# main.net
KiCad netlist of a schematic drawn in Altium Designer
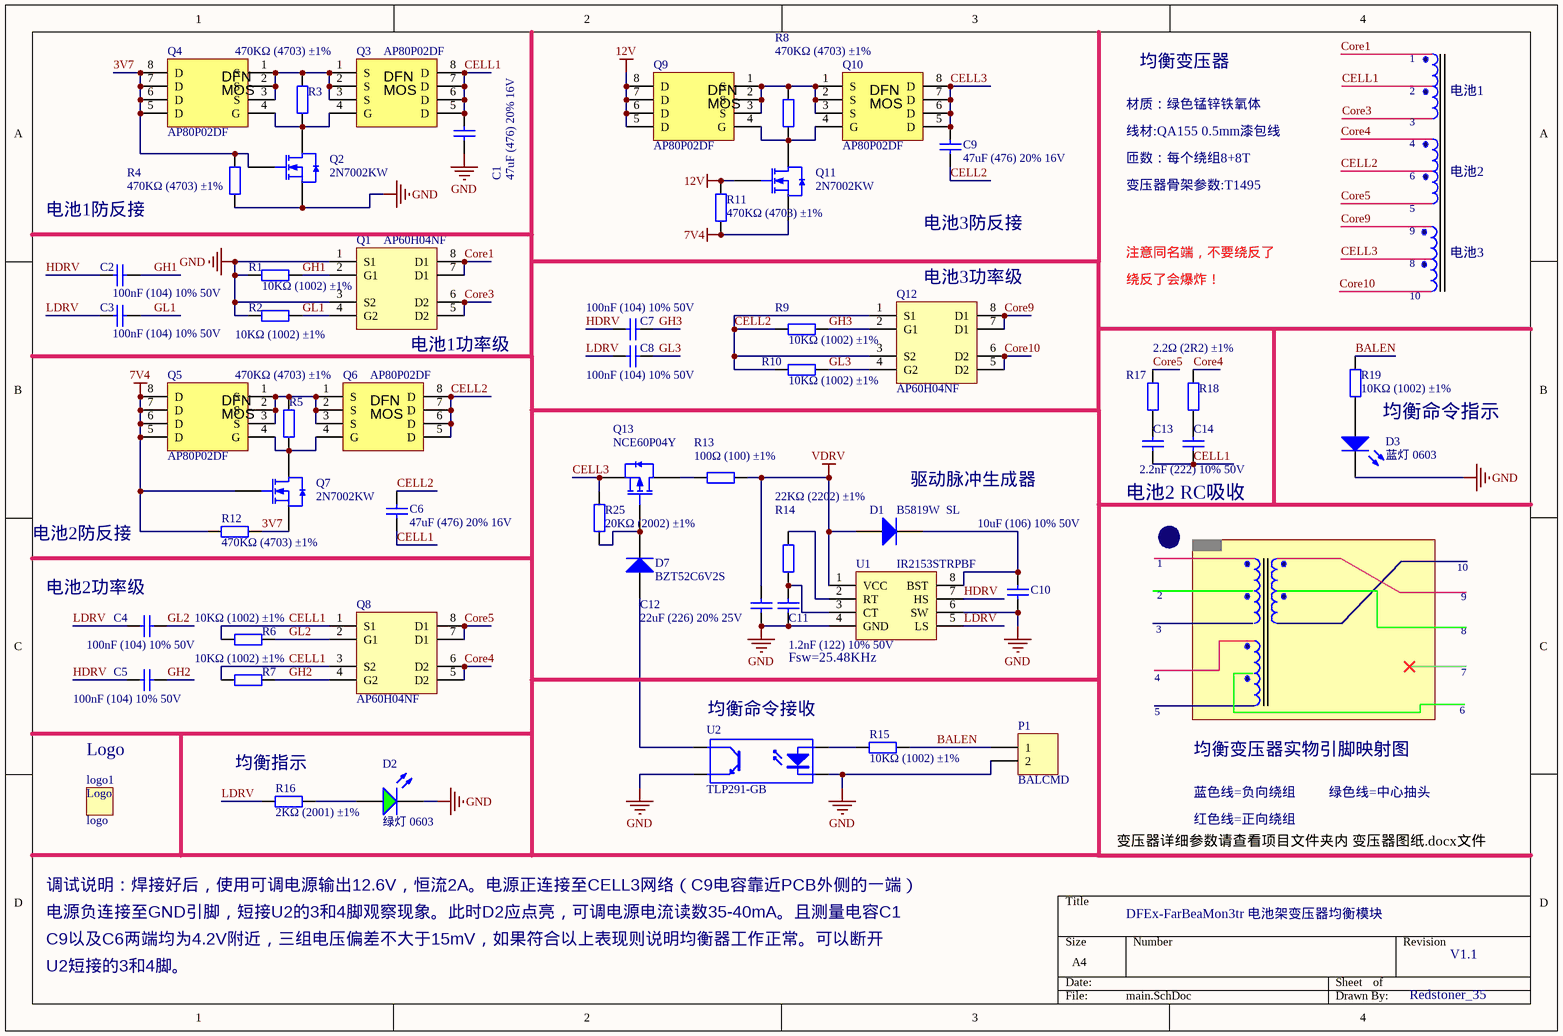
[diagram p0: main.SchDoc]

(export (version "E")
  (design (tool "Eeschema 10.0.6"))
  (components
    (comp (ref "C1")
      (value "47uF (476) 20% 16V")
      (footprint "1206_C")
      (description "贴片电容")
      (libsource (lib "Miscellaneous Devices LC") (part "1206 220pF (221) 10% 50V"))
    )
    (comp (ref "C2")
      (value "100nF (104) 10% 50V")
      (footprint "1206_C")
      (description "贴片电容")
      (libsource (lib "Miscellaneous Devices LC") (part "1206 100nF (104) 10% 50V"))
    )
    (comp (ref "C3")
      (value "100nF (104) 10% 50V")
      (footprint "1206_C")
      (description "贴片电容")
      (libsource (lib "Miscellaneous Devices LC") (part "1206 100nF (104) 10% 50V"))
    )
    (comp (ref "C4")
      (value "100nF (104) 10% 50V")
      (footprint "1206_C")
      (description "贴片电容")
      (libsource (lib "Miscellaneous Devices LC") (part "1206 100nF (104) 10% 50V"))
    )
    (comp (ref "C5")
      (value "100nF (104) 10% 50V")
      (footprint "1206_C")
      (description "贴片电容")
      (libsource (lib "Miscellaneous Devices LC") (part "1206 100nF (104) 10% 50V"))
    )
    (comp (ref "C6")
      (value "47uF (476) 20% 16V")
      (footprint "1206_C")
      (description "贴片电容")
      (libsource (lib "Miscellaneous Devices LC") (part "1206 220pF (221) 10% 50V"))
    )
    (comp (ref "C7")
      (value "100nF (104) 10% 50V")
      (footprint "1206_C")
      (description "贴片电容")
      (libsource (lib "Miscellaneous Devices LC") (part "1206 100nF (104) 10% 50V"))
    )
    (comp (ref "C8")
      (value "100nF (104) 10% 50V")
      (footprint "1206_C")
      (description "贴片电容")
      (libsource (lib "Miscellaneous Devices LC") (part "1206 100nF (104) 10% 50V"))
    )
    (comp (ref "C9")
      (value "47uF (476) 20% 16V")
      (footprint "1206_C")
      (description "贴片电容")
      (libsource (lib "Miscellaneous Devices LC") (part "1206 220pF (221) 10% 50V"))
    )
    (comp (ref "C10")
      (value "10uF (106) 10% 50V")
      (footprint "1206_C")
      (description "贴片电容")
      (libsource (lib "Miscellaneous Devices LC") (part "1206 10uF (106) 10% 50V"))
    )
    (comp (ref "C11")
      (value "1.2nF (122) 10% 50V")
      (footprint "0402_C")
      (description "贴片电容")
      (libsource (lib "Miscellaneous Devices LC") (part "0402 1nF (102) 10% 50V"))
    )
    (comp (ref "C12")
      (value "22uF (226) 20% 25V")
      (footprint "0805_C")
      (description "贴片电容")
      (libsource (lib "Miscellaneous Devices LC") (part "0805 22uF (226) 20% 25V"))
    )
    (comp (ref "C13")
      (value "2.2nF (222) 10% 50V")
      (footprint "0402_C")
      (description "贴片电容")
      (libsource (lib "Miscellaneous Devices LC") (part "0402 2.2nF (222) 10% 50V"))
    )
    (comp (ref "C14")
      (value "2.2nF (222) 10% 50V")
      (footprint "0402_C")
      (description "贴片电容")
      (libsource (lib "Miscellaneous Devices LC") (part "0402 2.2nF (222) 10% 50V"))
    )
    (comp (ref "D1")
      (value "B5819W  SL")
      (footprint "SOD-123")
      (description "肖特基二极管")
      (libsource (lib "Miscellaneous Devices LC") (part "SOD-123 B5819W  SL"))
    )
    (comp (ref "D2")
      (value "绿灯 0603")
      (footprint "0603_LED_S1")
      (description "发光二极管")
      (libsource (lib "Miscellaneous Devices LC") (part "0603 绿灯"))
    )
    (comp (ref "D3")
      (value "蓝灯 0603")
      (footprint "0603_LED_S1")
      (description "发光二极管")
      (libsource (lib "Miscellaneous Devices LC") (part "0603 蓝灯"))
    )
    (comp (ref "D7")
      (value "BZT52C6V2S")
      (footprint "SOD-323")
      (description "SOD-323稳压二极管 6.2V稳压电压")
      (libsource (lib "Miscellaneous Devices LC") (part "SOD-323 1N4148WS T4"))
    )
    (comp (ref "logo1")
      (value "logo")
      (footprint "HIGH-VOLTAGE-2")
      (libsource (lib "山猫的集成库20190318") (part "logo"))
    )
    (comp (ref "P1")
      (value "BALCMD")
      (footprint "PH2.0-WS-2P")
      (description "2-Pin")
      (fields (field (name "PUBLISHER") "Altium Limited"))
      (libsource (lib "山猫的集成库20190318") (part "CON 2"))
    )
    (comp (ref "Q1")
      (value "AP60H04NF")
      (footprint "Dual SSO8")
      (description "APM双N沟道MOS管，DFN56封装，40V/60A 4.8mΩ/4.5V Vgs")
      (libsource (lib "custom") (part "AP60H04NF"))
    )
    (comp (ref "Q2")
      (value "2N7002KW")
      (footprint "SC70-3")
      (description "单N沟道MOSFET(场效应管)")
      (libsource (lib "Miscellaneous Devices LC") (part "2N7002 7002"))
    )
    (comp (ref "Q3")
      (value "AP80P02DF")
      (footprint "DFN-8_L3.0-W3.0-P0.65-BL")
      (description "PDFN3x3 20V 50A 5.8mΩ N-Ch MOSFET")
      (libsource (lib "custom") (part "SON/DFN5x6 MOS"))
    )
    (comp (ref "Q4")
      (value "AP80P02DF")
      (footprint "DFN-8_L3.0-W3.0-P0.65-BL")
      (description "PDFN3x3 20V 50A 5.8mΩ N-Ch MOSFET")
      (libsource (lib "") (part "SON/DFN5x6 MOS_1"))
    )
    (comp (ref "Q5")
      (value "AP80P02DF")
      (footprint "DFN-8_L3.0-W3.0-P0.65-BL")
      (description "PDFN3x3 20V 50A 5.8mΩ N-Ch MOSFET")
      (libsource (lib "") (part "SON/DFN5x6 MOS_1"))
    )
    (comp (ref "Q6")
      (value "AP80P02DF")
      (footprint "DFN-8_L3.0-W3.0-P0.65-BL")
      (description "PDFN3x3 20V 50A 5.8mΩ N-Ch MOSFET")
      (libsource (lib "custom") (part "SON/DFN5x6 MOS"))
    )
    (comp (ref "Q7")
      (value "2N7002KW")
      (footprint "SC70-3")
      (description "单N沟道MOSFET(场效应管)")
      (libsource (lib "Miscellaneous Devices LC") (part "2N7002 7002"))
    )
    (comp (ref "Q8")
      (value "AP60H04NF")
      (footprint "Dual SSO8")
      (description "APM双N沟道MOS管，DFN56封装，40V/60A 4.8mΩ/4.5V Vgs")
      (libsource (lib "custom") (part "AP60H04NF"))
    )
    (comp (ref "Q9")
      (value "AP80P02DF")
      (footprint "DFN-8_L3.0-W3.0-P0.65-BL")
      (description "PDFN3x3 20V 50A 5.8mΩ N-Ch MOSFET")
      (libsource (lib "") (part "SON/DFN5x6 MOS_1"))
    )
    (comp (ref "Q10")
      (value "AP80P02DF")
      (footprint "DFN-8_L3.0-W3.0-P0.65-BL")
      (description "PDFN3x3 20V 50A 5.8mΩ N-Ch MOSFET")
      (libsource (lib "custom") (part "SON/DFN5x6 MOS"))
    )
    (comp (ref "Q11")
      (value "2N7002KW")
      (footprint "SC70-3")
      (description "单N沟道MOSFET(场效应管)")
      (libsource (lib "Miscellaneous Devices LC") (part "2N7002 7002"))
    )
    (comp (ref "Q12")
      (value "AP60H04NF")
      (footprint "Dual SSO8")
      (description "APM双N沟道MOS管，DFN56封装，40V/60A 4.8mΩ/4.5V Vgs")
      (libsource (lib "custom") (part "AP60H04NF"))
    )
    (comp (ref "Q13")
      (value "NCE60P04Y")
      (footprint "SOT-23(SOT-23-3)")
      (description "MOS(场效应管)")
      (libsource (lib "Miscellaneous Devices LC") (part "SI2301CDS-T1-GE3"))
    )
    (comp (ref "R1")
      (value "10KΩ (1002) ±1%")
      (footprint "0402_R")
      (description "贴片电阻")
      (libsource (lib "Miscellaneous Devices LC") (part "0402 10KΩ (1002) 1%"))
    )
    (comp (ref "R2")
      (value "10KΩ (1002) ±1%")
      (footprint "0402_R")
      (description "贴片电阻")
      (libsource (lib "Miscellaneous Devices LC") (part "0402 10KΩ (1002) 1%"))
    )
    (comp (ref "R3")
      (value "470KΩ (4703) ±1%")
      (footprint "0402_R")
      (description "贴片电阻")
      (libsource (lib "Miscellaneous Devices LC") (part "0402 470KΩ (4703) 1%"))
    )
    (comp (ref "R4")
      (value "470KΩ (4703) ±1%")
      (footprint "0402_R")
      (description "贴片电阻")
      (libsource (lib "Miscellaneous Devices LC") (part "0402 470KΩ (4703) 1%"))
    )
    (comp (ref "R5")
      (value "470KΩ (4703) ±1%")
      (footprint "0402_R")
      (description "贴片电阻")
      (libsource (lib "Miscellaneous Devices LC") (part "0402 470KΩ (4703) 1%"))
    )
    (comp (ref "R6")
      (value "10KΩ (1002) ±1%")
      (footprint "0402_R")
      (description "贴片电阻")
      (libsource (lib "Miscellaneous Devices LC") (part "0402 10KΩ (1002) 1%"))
    )
    (comp (ref "R7")
      (value "10KΩ (1002) ±1%")
      (footprint "0402_R")
      (description "贴片电阻")
      (libsource (lib "Miscellaneous Devices LC") (part "0402 10KΩ (1002) 1%"))
    )
    (comp (ref "R8")
      (value "470KΩ (4703) ±1%")
      (footprint "0402_R")
      (description "贴片电阻")
      (libsource (lib "Miscellaneous Devices LC") (part "0402 470KΩ (4703) 1%"))
    )
    (comp (ref "R9")
      (value "10KΩ (1002) ±1%")
      (footprint "0402_R")
      (description "贴片电阻")
      (libsource (lib "Miscellaneous Devices LC") (part "0402 10KΩ (1002) 1%"))
    )
    (comp (ref "R10")
      (value "10KΩ (1002) ±1%")
      (footprint "0402_R")
      (description "贴片电阻")
      (libsource (lib "Miscellaneous Devices LC") (part "0402 10KΩ (1002) 1%"))
    )
    (comp (ref "R11")
      (value "470KΩ (4703) ±1%")
      (footprint "0402_R")
      (description "贴片电阻")
      (libsource (lib "Miscellaneous Devices LC") (part "0402 470KΩ (4703) 1%"))
    )
    (comp (ref "R12")
      (value "470KΩ (4703) ±1%")
      (footprint "0402_R")
      (description "贴片电阻")
      (libsource (lib "") (part "0402 470KΩ (4703) 1%_1"))
    )
    (comp (ref "R13")
      (value "100Ω (100) ±1%")
      (footprint "1206_R")
      (description "贴片电阻")
      (libsource (lib "Miscellaneous Devices LC") (part "1206 4.7KΩ (4701) 1%"))
    )
    (comp (ref "R14")
      (value "22KΩ (2202) ±1%")
      (footprint "0402_R")
      (description "贴片电阻")
      (libsource (lib "Miscellaneous Devices LC") (part "0402 39KΩ (3902) 1%"))
    )
    (comp (ref "R15")
      (value "10KΩ (1002) ±1%")
      (footprint "0402_R")
      (description "贴片电阻")
      (libsource (lib "Miscellaneous Devices LC") (part "0402 10KΩ (1002) 1%"))
    )
    (comp (ref "R16")
      (value "2KΩ (2001) ±1%")
      (footprint "0402_R")
      (description "贴片电阻")
      (libsource (lib "Miscellaneous Devices LC") (part "0402 2KΩ (2001) 1%"))
    )
    (comp (ref "R17")
      (value "2.2Ω (2R2) ±1%")
      (footprint "0402_R")
      (description "贴片电阻")
      (libsource (lib "Miscellaneous Devices LC") (part "0402 1Ω (1R00) 1%"))
    )
    (comp (ref "R18")
      (value "2.2Ω (2R2) ±1%")
      (footprint "0402_R")
      (description "贴片电阻")
      (libsource (lib "Miscellaneous Devices LC") (part "0402 1Ω (1R00) 1%"))
    )
    (comp (ref "R19")
      (value "10KΩ (1002) ±1%")
      (footprint "0402_R")
      (description "贴片电阻")
      (libsource (lib "") (part "0402 10KΩ (1002) 1%_1"))
    )
    (comp (ref "R25")
      (value "20KΩ (2002) ±1%")
      (footprint "0402_R")
      (description "贴片电阻")
      (libsource (lib "Miscellaneous Devices LC") (part "0402 20KΩ (2002) 1%"))
    )
    (comp (ref "U1")
      (value "IR2153STRPBF")
      (footprint "SO8_N")
      (description "600V耐压，自震荡具备死区时间的2A峰值驱动能力半桥驱动芯片")
      (libsource (lib "custom") (part "EG2153"))
    )
    (comp (ref "U2")
      (value "TLP291-GB")
      (footprint "SOP127P700X210-4M")
      (description "4-Pin Phototransistor Optocoupler")
      (fields (field (name "PUBLISHER") "Altium Limited"))
      (libsource (lib "Miscellaneous Devices") (part "Optoisolator1"))
    )
  )
  (nets
    (net (code "1") (name "/3V7") (class "Default")
      (node (ref "Q2") (pin "1") (pinfunction "G_1") (pintype "passive"))
      (node (ref "Q4") (pin "5") (pinfunction "D_5") (pintype "passive"))
      (node (ref "Q4") (pin "6") (pinfunction "D_6") (pintype "passive"))
      (node (ref "Q4") (pin "7") (pinfunction "D_7") (pintype "passive"))
      (node (ref "Q4") (pin "8") (pinfunction "D_8") (pintype "passive"))
      (node (ref "Q7") (pin "2") (pinfunction "S_2") (pintype "passive"))
      (node (ref "R12") (pin "1") (pinfunction "1_1") (pintype "passive"))
      (node (ref "R4") (pin "2") (pinfunction "2_2") (pintype "passive"))
    )
    (net (code "2") (name "/BALEN") (class "Default")
      (node (ref "P1") (pin "1") (pinfunction "1_1") (pintype "passive"))
      (node (ref "R15") (pin "2") (pinfunction "2_2") (pintype "passive"))
      (node (ref "R19") (pin "2") (pinfunction "2_2") (pintype "passive"))
    )
    (net (code "3") (name "/CELL1") (class "Default")
      (node (ref "C1") (pin "2") (pinfunction "2_2") (pintype "passive"))
      (node (ref "C13") (pin "1") (pinfunction "1_1") (pintype "passive"))
      (node (ref "C14") (pin "1") (pinfunction "1_1") (pintype "passive"))
      (node (ref "C6") (pin "1") (pinfunction "1_1") (pintype "passive"))
      (node (ref "Q3") (pin "5") (pinfunction "D_5") (pintype "passive"))
      (node (ref "Q3") (pin "6") (pinfunction "D_6") (pintype "passive"))
      (node (ref "Q3") (pin "7") (pinfunction "D_7") (pintype "passive"))
      (node (ref "Q3") (pin "8") (pinfunction "D_8") (pintype "passive"))
      (node (ref "Q8") (pin "1") (pinfunction "S1_1") (pintype "passive"))
      (node (ref "Q8") (pin "3") (pinfunction "S2_3") (pintype "passive"))
      (node (ref "R6") (pin "1") (pinfunction "1_1") (pintype "passive"))
      (node (ref "R7") (pin "1") (pinfunction "1_1") (pintype "passive"))
    )
    (net (code "4") (name "/CELL2") (class "Default")
      (node (ref "C6") (pin "2") (pinfunction "2_2") (pintype "passive"))
      (node (ref "C9") (pin "1") (pinfunction "1_1") (pintype "passive"))
      (node (ref "Q12") (pin "1") (pinfunction "S1_1") (pintype "passive"))
      (node (ref "Q12") (pin "3") (pinfunction "S2_3") (pintype "passive"))
      (node (ref "Q6") (pin "5") (pinfunction "D_5") (pintype "passive"))
      (node (ref "Q6") (pin "6") (pinfunction "D_6") (pintype "passive"))
      (node (ref "Q6") (pin "7") (pinfunction "D_7") (pintype "passive"))
      (node (ref "Q6") (pin "8") (pinfunction "D_8") (pintype "passive"))
      (node (ref "R10") (pin "1") (pinfunction "1_1") (pintype "passive"))
      (node (ref "R9") (pin "1") (pinfunction "1_1") (pintype "passive"))
    )
    (net (code "5") (name "/CELL3") (class "Default")
      (node (ref "C9") (pin "2") (pinfunction "2_2") (pintype "passive"))
      (node (ref "Q10") (pin "5") (pinfunction "D_5") (pintype "passive"))
      (node (ref "Q10") (pin "6") (pinfunction "D_6") (pintype "passive"))
      (node (ref "Q10") (pin "7") (pinfunction "D_7") (pintype "passive"))
      (node (ref "Q10") (pin "8") (pinfunction "D_8") (pintype "passive"))
      (node (ref "Q13") (pin "2") (pinfunction "S_2") (pintype "passive"))
      (node (ref "R25") (pin "2") (pinfunction "2_2") (pintype "passive"))
    )
    (net (code "6") (name "/Core1") (class "Default")
      (node (ref "Q1") (pin "7") (pinfunction "D1_7") (pintype "passive"))
      (node (ref "Q1") (pin "8") (pinfunction "D1_8") (pintype "passive"))
    )
    (net (code "7") (name "/Core3") (class "Default")
      (node (ref "Q1") (pin "5") (pinfunction "D2_5") (pintype "passive"))
      (node (ref "Q1") (pin "6") (pinfunction "D2_6") (pintype "passive"))
    )
    (net (code "8") (name "/Core4") (class "Default")
      (node (ref "Q8") (pin "5") (pinfunction "D2_5") (pintype "passive"))
      (node (ref "Q8") (pin "6") (pinfunction "D2_6") (pintype "passive"))
      (node (ref "R18") (pin "2") (pinfunction "2_2") (pintype "passive"))
    )
    (net (code "9") (name "/Core5") (class "Default")
      (node (ref "Q8") (pin "7") (pinfunction "D1_7") (pintype "passive"))
      (node (ref "Q8") (pin "8") (pinfunction "D1_8") (pintype "passive"))
      (node (ref "R17") (pin "2") (pinfunction "2_2") (pintype "passive"))
    )
    (net (code "10") (name "/Core9") (class "Default")
      (node (ref "Q12") (pin "7") (pinfunction "D1_7") (pintype "passive"))
      (node (ref "Q12") (pin "8") (pinfunction "D1_8") (pintype "passive"))
    )
    (net (code "11") (name "/Core10") (class "Default")
      (node (ref "Q12") (pin "5") (pinfunction "D2_5") (pintype "passive"))
      (node (ref "Q12") (pin "6") (pinfunction "D2_6") (pintype "passive"))
    )
    (net (code "12") (name "/GH1") (class "Default")
      (node (ref "C2") (pin "2") (pinfunction "2_2") (pintype "passive"))
      (node (ref "Q1") (pin "2") (pinfunction "G1_2") (pintype "passive"))
      (node (ref "R1") (pin "2") (pinfunction "2_2") (pintype "passive"))
    )
    (net (code "13") (name "/GH2") (class "Default")
      (node (ref "C5") (pin "2") (pinfunction "2_2") (pintype "passive"))
      (node (ref "Q8") (pin "4") (pinfunction "G2_4") (pintype "passive"))
      (node (ref "R7") (pin "2") (pinfunction "2_2") (pintype "passive"))
    )
    (net (code "14") (name "/GH3") (class "Default")
      (node (ref "C7") (pin "2") (pinfunction "2_2") (pintype "passive"))
      (node (ref "Q12") (pin "2") (pinfunction "G1_2") (pintype "passive"))
      (node (ref "R9") (pin "2") (pinfunction "2_2") (pintype "passive"))
    )
    (net (code "15") (name "/GL1") (class "Default")
      (node (ref "C3") (pin "2") (pinfunction "2_2") (pintype "passive"))
      (node (ref "Q1") (pin "4") (pinfunction "G2_4") (pintype "passive"))
      (node (ref "R2") (pin "2") (pinfunction "2_2") (pintype "passive"))
    )
    (net (code "16") (name "/GL2") (class "Default")
      (node (ref "C4") (pin "2") (pinfunction "2_2") (pintype "passive"))
      (node (ref "Q8") (pin "2") (pinfunction "G1_2") (pintype "passive"))
      (node (ref "R6") (pin "2") (pinfunction "2_2") (pintype "passive"))
    )
    (net (code "17") (name "/GL3") (class "Default")
      (node (ref "C8") (pin "2") (pinfunction "2_2") (pintype "passive"))
      (node (ref "Q12") (pin "4") (pinfunction "G2_4") (pintype "passive"))
      (node (ref "R10") (pin "2") (pinfunction "2_2") (pintype "passive"))
    )
    (net (code "18") (name "/HDRV") (class "Default")
      (node (ref "C2") (pin "1") (pinfunction "1_1") (pintype "passive"))
      (node (ref "C5") (pin "1") (pinfunction "1_1") (pintype "passive"))
      (node (ref "C7") (pin "1") (pinfunction "1_1") (pintype "passive"))
      (node (ref "U1") (pin "7") (pinfunction "HS_7") (pintype "passive"))
    )
    (net (code "19") (name "/LDRV") (class "Default")
      (node (ref "C3") (pin "1") (pinfunction "1_1") (pintype "passive"))
      (node (ref "C4") (pin "1") (pinfunction "1_1") (pintype "passive"))
      (node (ref "C8") (pin "1") (pinfunction "1_1") (pintype "passive"))
      (node (ref "R16") (pin "1") (pinfunction "1_1") (pintype "passive"))
      (node (ref "U1") (pin "5") (pinfunction "LS_5") (pintype "passive"))
    )
    (net (code "20") (name "7V4") (class "Default")
      (node (ref "Q11") (pin "2") (pinfunction "S_2") (pintype "passive"))
      (node (ref "Q5") (pin "5") (pinfunction "D_5") (pintype "passive"))
      (node (ref "Q5") (pin "6") (pinfunction "D_6") (pintype "passive"))
      (node (ref "Q5") (pin "7") (pinfunction "D_7") (pintype "passive"))
      (node (ref "Q5") (pin "8") (pinfunction "D_8") (pintype "passive"))
      (node (ref "Q7") (pin "1") (pinfunction "G_1") (pintype "passive"))
      (node (ref "R11") (pin "1") (pinfunction "1_1") (pintype "passive"))
      (node (ref "R12") (pin "2") (pinfunction "2_2") (pintype "passive"))
    )
    (net (code "21") (name "12V") (class "Default")
      (node (ref "Q11") (pin "1") (pinfunction "G_1") (pintype "passive"))
      (node (ref "Q9") (pin "5") (pinfunction "D_5") (pintype "passive"))
      (node (ref "Q9") (pin "6") (pinfunction "D_6") (pintype "passive"))
      (node (ref "Q9") (pin "7") (pinfunction "D_7") (pintype "passive"))
      (node (ref "Q9") (pin "8") (pinfunction "D_8") (pintype "passive"))
      (node (ref "R11") (pin "2") (pinfunction "2_2") (pintype "passive"))
    )
    (net (code "22") (name "GND") (class "Default")
      (node (ref "C1") (pin "1") (pinfunction "1_1") (pintype "passive"))
      (node (ref "C10") (pin "1") (pinfunction "1_1") (pintype "passive"))
      (node (ref "C11") (pin "1") (pinfunction "1_1") (pintype "passive"))
      (node (ref "C12") (pin "1") (pinfunction "1_1") (pintype "passive"))
      (node (ref "D2") (pin "K") (pinfunction "K_K") (pintype "passive"))
      (node (ref "D3") (pin "K") (pinfunction "K_K") (pintype "passive"))
      (node (ref "P1") (pin "2") (pinfunction "2_2") (pintype "passive"))
      (node (ref "Q1") (pin "1") (pinfunction "S1_1") (pintype "passive"))
      (node (ref "Q1") (pin "3") (pinfunction "S2_3") (pintype "passive"))
      (node (ref "Q2") (pin "2") (pinfunction "S_2") (pintype "passive"))
      (node (ref "R1") (pin "1") (pinfunction "1_1") (pintype "passive"))
      (node (ref "R2") (pin "1") (pinfunction "1_1") (pintype "passive"))
      (node (ref "R4") (pin "1") (pinfunction "1_1") (pintype "passive"))
      (node (ref "U1") (pin "4") (pinfunction "GND_4") (pintype "passive"))
      (node (ref "U1") (pin "6") (pinfunction "SW_6") (pintype "passive"))
      (node (ref "U2") (pin "2") (pinfunction "K_2") (pintype "passive"))
      (node (ref "U2") (pin "3") (pinfunction "E_3") (pintype "passive"))
    )
    (net (code "23") (name "Net-(C13-Pad2)") (class "Default")
      (node (ref "C13") (pin "2") (pinfunction "2_2") (pintype "passive"))
      (node (ref "R17") (pin "1") (pinfunction "1_1") (pintype "passive"))
    )
    (net (code "24") (name "Net-(C14-Pad2)") (class "Default")
      (node (ref "C14") (pin "2") (pinfunction "2_2") (pintype "passive"))
      (node (ref "R18") (pin "1") (pinfunction "1_1") (pintype "passive"))
    )
    (net (code "25") (name "Net-(D1-K)") (class "Default")
      (node (ref "C10") (pin "2") (pinfunction "2_2") (pintype "passive"))
      (node (ref "D1") (pin "2") (pinfunction "K_2") (pintype "passive"))
      (node (ref "U1") (pin "8") (pinfunction "BST_8") (pintype "passive"))
    )
    (net (code "26") (name "Net-(D2-PadA)") (class "Default")
      (node (ref "D2") (pin "A") (pinfunction "A_A") (pintype "passive"))
      (node (ref "R16") (pin "2") (pinfunction "2_2") (pintype "passive"))
    )
    (net (code "27") (name "Net-(D3-PadA)") (class "Default")
      (node (ref "D3") (pin "A") (pinfunction "A_A") (pintype "passive"))
      (node (ref "R19") (pin "1") (pinfunction "1_1") (pintype "passive"))
    )
    (net (code "28") (name "Net-(D7-A)") (class "Default")
      (node (ref "D7") (pin "1") (pinfunction "A_1") (pintype "passive"))
      (node (ref "U2") (pin "4") (pinfunction "C_4") (pintype "passive"))
    )
    (net (code "29") (name "Net-(D7-K)") (class "Default")
      (node (ref "D7") (pin "2") (pinfunction "K_2") (pintype "passive"))
      (node (ref "Q13") (pin "1") (pinfunction "G_1") (pintype "passive"))
      (node (ref "R25") (pin "1") (pinfunction "1_1") (pintype "passive"))
    )
    (net (code "30") (name "Net-(Q2-D)") (class "Default")
      (node (ref "Q2") (pin "3") (pinfunction "D_3") (pintype "passive"))
      (node (ref "Q3") (pin "4") (pinfunction "G_4") (pintype "passive"))
      (node (ref "Q4") (pin "4") (pinfunction "G_4") (pintype "passive"))
      (node (ref "R3") (pin "1") (pinfunction "1_1") (pintype "passive"))
    )
    (net (code "31") (name "Net-(Q3-S-Pad1)") (class "Default")
      (node (ref "Q3") (pin "1") (pinfunction "S_1") (pintype "passive"))
      (node (ref "Q3") (pin "2") (pinfunction "S_2") (pintype "passive"))
      (node (ref "Q3") (pin "3") (pinfunction "S_3") (pintype "passive"))
      (node (ref "Q4") (pin "1") (pinfunction "S_1") (pintype "passive"))
      (node (ref "Q4") (pin "2") (pinfunction "S_2") (pintype "passive"))
      (node (ref "Q4") (pin "3") (pinfunction "S_3") (pintype "passive"))
      (node (ref "R3") (pin "2") (pinfunction "2_2") (pintype "passive"))
    )
    (net (code "32") (name "Net-(Q5-G)") (class "Default")
      (node (ref "Q5") (pin "4") (pinfunction "G_4") (pintype "passive"))
      (node (ref "Q6") (pin "4") (pinfunction "G_4") (pintype "passive"))
      (node (ref "Q7") (pin "3") (pinfunction "D_3") (pintype "passive"))
      (node (ref "R5") (pin "1") (pinfunction "1_1") (pintype "passive"))
    )
    (net (code "33") (name "Net-(Q5-S-Pad1)") (class "Default")
      (node (ref "Q5") (pin "1") (pinfunction "S_1") (pintype "passive"))
      (node (ref "Q5") (pin "2") (pinfunction "S_2") (pintype "passive"))
      (node (ref "Q5") (pin "3") (pinfunction "S_3") (pintype "passive"))
      (node (ref "Q6") (pin "1") (pinfunction "S_1") (pintype "passive"))
      (node (ref "Q6") (pin "2") (pinfunction "S_2") (pintype "passive"))
      (node (ref "Q6") (pin "3") (pinfunction "S_3") (pintype "passive"))
      (node (ref "R5") (pin "2") (pinfunction "2_2") (pintype "passive"))
    )
    (net (code "34") (name "Net-(Q10-G)") (class "Default")
      (node (ref "Q10") (pin "4") (pinfunction "G_4") (pintype "passive"))
      (node (ref "Q11") (pin "3") (pinfunction "D_3") (pintype "passive"))
      (node (ref "Q9") (pin "4") (pinfunction "G_4") (pintype "passive"))
      (node (ref "R8") (pin "1") (pinfunction "1_1") (pintype "passive"))
    )
    (net (code "35") (name "Net-(Q10-S-Pad1)") (class "Default")
      (node (ref "Q10") (pin "1") (pinfunction "S_1") (pintype "passive"))
      (node (ref "Q10") (pin "2") (pinfunction "S_2") (pintype "passive"))
      (node (ref "Q10") (pin "3") (pinfunction "S_3") (pintype "passive"))
      (node (ref "Q9") (pin "1") (pinfunction "S_1") (pintype "passive"))
      (node (ref "Q9") (pin "2") (pinfunction "S_2") (pintype "passive"))
      (node (ref "Q9") (pin "3") (pinfunction "S_3") (pintype "passive"))
      (node (ref "R8") (pin "2") (pinfunction "2_2") (pintype "passive"))
    )
    (net (code "36") (name "Net-(Q13-D)") (class "Default")
      (node (ref "Q13") (pin "3") (pinfunction "D_3") (pintype "passive"))
      (node (ref "R13") (pin "1") (pinfunction "1_1") (pintype "passive"))
    )
    (net (code "37") (name "Net-(U1-CT)") (class "Default")
      (node (ref "C11") (pin "2") (pinfunction "2_2") (pintype "passive"))
      (node (ref "R14") (pin "1") (pinfunction "1_1") (pintype "passive"))
      (node (ref "U1") (pin "3") (pinfunction "CT_3") (pintype "passive"))
    )
    (net (code "38") (name "Net-(U1-RT)") (class "Default")
      (node (ref "R14") (pin "2") (pinfunction "2_2") (pintype "passive"))
      (node (ref "U1") (pin "2") (pinfunction "RT_2") (pintype "passive"))
    )
    (net (code "39") (name "Net-(U2-A)") (class "Default")
      (node (ref "R15") (pin "1") (pinfunction "1_1") (pintype "passive"))
      (node (ref "U2") (pin "1") (pinfunction "A_1") (pintype "passive"))
    )
    (net (code "40") (name "VDRV") (class "Default")
      (node (ref "C12") (pin "2") (pinfunction "2_2") (pintype "passive"))
      (node (ref "D1") (pin "1") (pinfunction "A_1") (pintype "passive"))
      (node (ref "R13") (pin "2") (pinfunction "2_2") (pintype "passive"))
      (node (ref "U1") (pin "1") (pinfunction "VCC_1") (pintype "power_in"))
    )
  )
)
